# alarmclock3.net
KiCad netlist of a schematic drawn in EAGLE
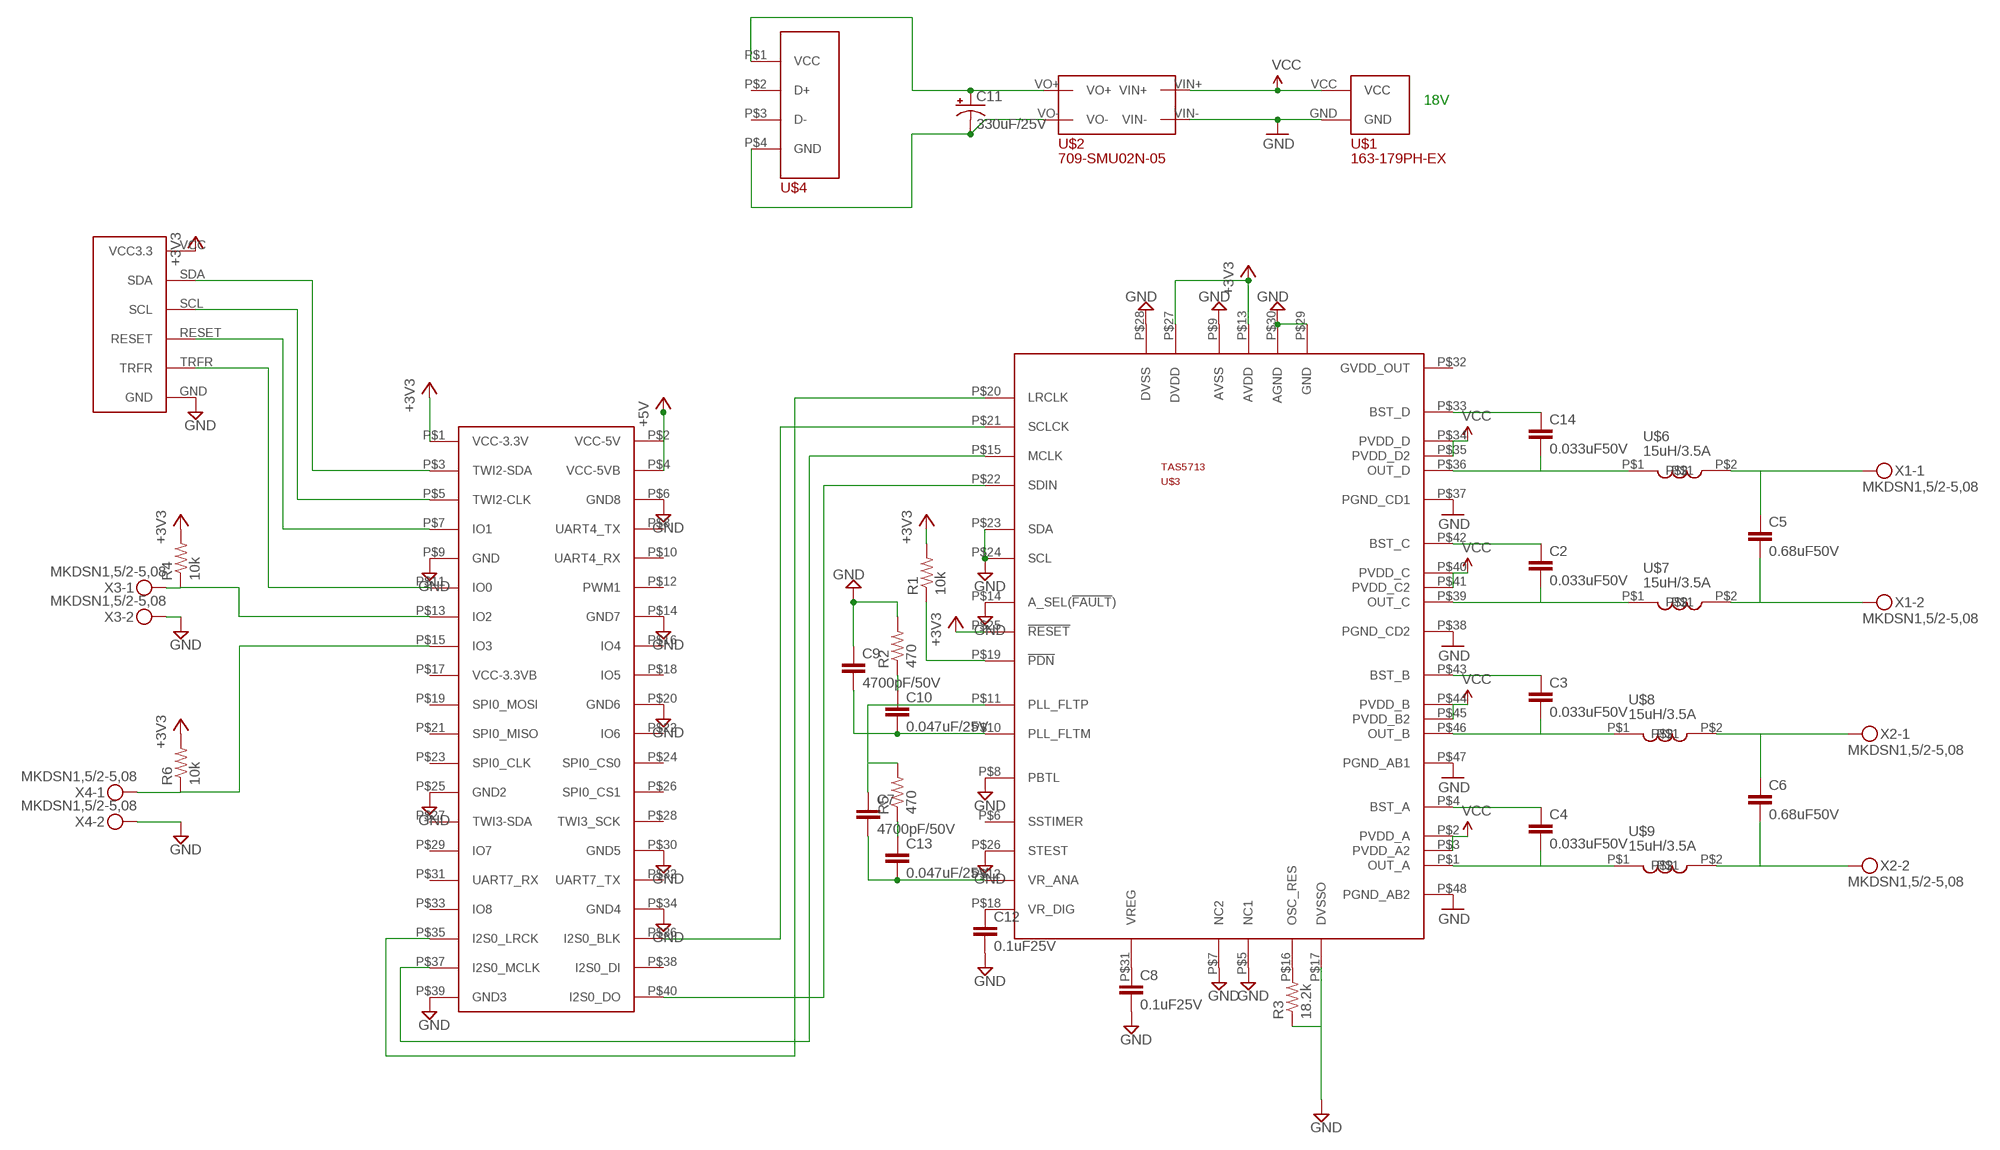
[diagram p0: schematic, sheet 1]

(export (version "E")
  (design (tool "Eeschema 10.0.6"))
  (components
    (comp (ref "C2")
      (value "0.033uF50V")
      (footprint "eagle-import:0603-CAP")
      (libsource (lib "eagle-import") (part "CAP0603-CAP"))
    )
    (comp (ref "C3")
      (value "0.033uF50V")
      (footprint "eagle-import:0603-CAP")
      (libsource (lib "eagle-import") (part "CAP0603-CAP"))
    )
    (comp (ref "C4")
      (value "0.033uF50V")
      (footprint "eagle-import:0603-CAP")
      (libsource (lib "eagle-import") (part "CAP0603-CAP"))
    )
    (comp (ref "C5")
      (value "0.68uF50V")
      (footprint "eagle-import:0603-CAP")
      (libsource (lib "eagle-import") (part "CAP0603-CAP"))
    )
    (comp (ref "C6")
      (value "0.68uF50V")
      (footprint "eagle-import:0603-CAP")
      (libsource (lib "eagle-import") (part "CAP0603-CAP"))
    )
    (comp (ref "C7")
      (value "4700pF/50V")
      (footprint "eagle-import:0603-CAP")
      (libsource (lib "eagle-import") (part "CAP0603-CAP"))
    )
    (comp (ref "C8")
      (value "0.1uF25V")
      (footprint "eagle-import:0603-CAP")
      (libsource (lib "eagle-import") (part "CAP0603-CAP"))
    )
    (comp (ref "C9")
      (value "4700pF/50V")
      (footprint "eagle-import:0603-CAP")
      (libsource (lib "eagle-import") (part "CAP0603-CAP"))
    )
    (comp (ref "C10")
      (value "0.047uF/25V")
      (footprint "eagle-import:0603-CAP")
      (libsource (lib "eagle-import") (part "CAP0603-CAP"))
    )
    (comp (ref "C11")
      (value "330uF/25V")
      (footprint "eagle-import:CPOL-RADIAL-10UF-25V")
      (libsource (lib "eagle-import") (part "CAP_POLPTH2"))
    )
    (comp (ref "C12")
      (value "0.1uF25V")
      (footprint "eagle-import:0603-CAP")
      (libsource (lib "eagle-import") (part "CAP0603-CAP"))
    )
    (comp (ref "C13")
      (value "0.047uF/25V")
      (footprint "eagle-import:0603-CAP")
      (libsource (lib "eagle-import") (part "CAP0603-CAP"))
    )
    (comp (ref "C14")
      (value "0.033uF50V")
      (footprint "eagle-import:0603-CAP")
      (libsource (lib "eagle-import") (part "CAP0603-CAP"))
    )
    (comp (ref "R1")
      (value "10k")
      (footprint "eagle-import:0603-RES")
      (libsource (lib "eagle-import") (part "RESISTOR0603-RES"))
    )
    (comp (ref "R2")
      (value "470")
      (footprint "eagle-import:0603-RES")
      (libsource (lib "eagle-import") (part "RESISTOR0603-RES"))
    )
    (comp (ref "R3")
      (value "18.2k")
      (footprint "eagle-import:0603-RES")
      (libsource (lib "eagle-import") (part "RESISTOR0603-RES"))
    )
    (comp (ref "R4")
      (value "10k")
      (footprint "eagle-import:0603-RES")
      (libsource (lib "eagle-import") (part "RESISTOR0603-RES"))
    )
    (comp (ref "R5")
      (value "470")
      (footprint "eagle-import:0603-RES")
      (libsource (lib "eagle-import") (part "RESISTOR0603-RES"))
    )
    (comp (ref "R6")
      (value "10k")
      (footprint "eagle-import:0603-RES")
      (libsource (lib "eagle-import") (part "RESISTOR0603-RES"))
    )
    (comp (ref "U$1")
      (value "163-179PH-EX")
      (footprint "eagle-import:163-179PH-EX_DIM")
      (libsource (lib "eagle-import") (part "163-179PH-EX"))
    )
    (comp (ref "U$2")
      (value "709-SMU02N-05")
      (footprint "eagle-import:709-SMU02N-05_DIM")
      (libsource (lib "eagle-import") (part "709-SMU02N-05"))
    )
    (comp (ref "U$3")
      (value "TAS5713")
      (footprint "eagle-import:TAS5713_DIM")
      (libsource (lib "eagle-import") (part "TAS5713"))
    )
    (comp (ref "U$4")
      (value "USB_TYPEA_CONNECTOR")
      (footprint "eagle-import:USB_DIM")
      (libsource (lib "eagle-import") (part "USB_TYPEA_CONNECTOR"))
    )
    (comp (ref "U$5")
      (value "BANANAPRO-CON6")
      (footprint "eagle-import:BANANAPRO-CON6_DIM")
      (libsource (lib "eagle-import") (part "BANANAPRO-CON6"))
    )
    (comp (ref "U$6")
      (value "15uH/3.5A")
      (footprint "eagle-import:MSS1260_DIM")
      (libsource (lib "eagle-import") (part "MSS1260INDUCTOR"))
    )
    (comp (ref "U$7")
      (value "15uH/3.5A")
      (footprint "eagle-import:MSS1260_DIM")
      (libsource (lib "eagle-import") (part "MSS1260INDUCTOR"))
    )
    (comp (ref "U$8")
      (value "15uH/3.5A")
      (footprint "eagle-import:MSS1260_DIM")
      (libsource (lib "eagle-import") (part "MSS1260INDUCTOR"))
    )
    (comp (ref "U$9")
      (value "15uH/3.5A")
      (footprint "eagle-import:MSS1260_DIM")
      (libsource (lib "eagle-import") (part "MSS1260INDUCTOR"))
    )
    (comp (ref "U$10")
      (value "SKYWRITER")
      (footprint "eagle-import:SKYWRITER_DIM")
      (libsource (lib "eagle-import") (part "SKYWRITER"))
    )
    (comp (ref "X1")
      (value "MKDSN1,5/2-5,08")
      (footprint "eagle-import:MKDSN1,5_2-5,08")
      (libsource (lib "eagle-import") (part "MKDSN1,5/2-5,08"))
    )
    (comp (ref "X2")
      (value "MKDSN1,5/2-5,08")
      (footprint "eagle-import:MKDSN1,5_2-5,08")
      (libsource (lib "eagle-import") (part "MKDSN1,5/2-5,08"))
    )
    (comp (ref "X3")
      (value "MKDSN1,5/2-5,08")
      (footprint "eagle-import:MKDSN1,5_2-5,08")
      (libsource (lib "eagle-import") (part "MKDSN1,5/2-5,08"))
    )
    (comp (ref "X4")
      (value "MKDSN1,5/2-5,08")
      (footprint "eagle-import:MKDSN1,5_2-5,08")
      (libsource (lib "eagle-import") (part "MKDSN1,5/2-5,08"))
    )
  )
  (nets
    (net (code "1") (name "+3V3") (class "Default")
      (node (ref "R1") (pin "2") (pinfunction "2_2") (pintype "passive"))
      (node (ref "R4") (pin "2") (pinfunction "2_2") (pintype "passive"))
      (node (ref "R6") (pin "2") (pinfunction "2_2") (pintype "passive"))
      (node (ref "U$10") (pin "VCC") (pinfunction "VCC3.3_VCC") (pintype "bidirectional"))
      (node (ref "U$3") (pin "P$13") (pinfunction "AVDD_P$13") (pintype "bidirectional"))
      (node (ref "U$3") (pin "P$25") (pinfunction "~{RESET}_P$25") (pintype "bidirectional"))
      (node (ref "U$3") (pin "P$27") (pinfunction "DVDD_P$27") (pintype "bidirectional"))
      (node (ref "U$5") (pin "P$1") (pinfunction "VCC-3.3V_P$1") (pintype "bidirectional"))
    )
    (net (code "2") (name "+5V") (class "Default")
      (node (ref "U$5") (pin "P$2") (pinfunction "VCC-5V_P$2") (pintype "bidirectional"))
      (node (ref "U$5") (pin "P$4") (pinfunction "VCC-5VB_P$4") (pintype "bidirectional"))
    )
    (net (code "3") (name "GND") (class "Default")
      (node (ref "C12") (pin "2") (pinfunction "2_2") (pintype "passive"))
      (node (ref "C8") (pin "2") (pinfunction "2_2") (pintype "passive"))
      (node (ref "C9") (pin "1") (pinfunction "1_1") (pintype "passive"))
      (node (ref "R2") (pin "2") (pinfunction "2_2") (pintype "passive"))
      (node (ref "R3") (pin "1") (pinfunction "1_1") (pintype "passive"))
      (node (ref "U$1") (pin "GND") (pinfunction "GND_GND") (pintype "bidirectional"))
      (node (ref "U$10") (pin "GND") (pinfunction "GND_GND") (pintype "bidirectional"))
      (node (ref "U$2") (pin "VIN-") (pinfunction "VIN-_VIN-") (pintype "bidirectional"))
      (node (ref "U$3") (pin "P$14") (pinfunction "A_SEL(~{FAULT})_P$14") (pintype "bidirectional"))
      (node (ref "U$3") (pin "P$17") (pinfunction "DVSSO_P$17") (pintype "bidirectional"))
      (node (ref "U$3") (pin "P$23") (pinfunction "SDA_P$23") (pintype "bidirectional"))
      (node (ref "U$3") (pin "P$24") (pinfunction "SCL_P$24") (pintype "bidirectional"))
      (node (ref "U$3") (pin "P$26") (pinfunction "STEST_P$26") (pintype "bidirectional"))
      (node (ref "U$3") (pin "P$28") (pinfunction "DVSS_P$28") (pintype "bidirectional"))
      (node (ref "U$3") (pin "P$29") (pinfunction "GND_P$29") (pintype "bidirectional"))
      (node (ref "U$3") (pin "P$30") (pinfunction "AGND_P$30") (pintype "bidirectional"))
      (node (ref "U$3") (pin "P$37") (pinfunction "PGND_CD1_P$37") (pintype "bidirectional"))
      (node (ref "U$3") (pin "P$38") (pinfunction "PGND_CD2_P$38") (pintype "bidirectional"))
      (node (ref "U$3") (pin "P$47") (pinfunction "PGND_AB1_P$47") (pintype "bidirectional"))
      (node (ref "U$3") (pin "P$48") (pinfunction "PGND_AB2_P$48") (pintype "bidirectional"))
      (node (ref "U$3") (pin "P$5") (pinfunction "NC1_P$5") (pintype "bidirectional"))
      (node (ref "U$3") (pin "P$7") (pinfunction "NC2_P$7") (pintype "bidirectional"))
      (node (ref "U$3") (pin "P$8") (pinfunction "PBTL_P$8") (pintype "bidirectional"))
      (node (ref "U$3") (pin "P$9") (pinfunction "AVSS_P$9") (pintype "bidirectional"))
      (node (ref "U$5") (pin "P$14") (pinfunction "GND7_P$14") (pintype "bidirectional"))
      (node (ref "U$5") (pin "P$20") (pinfunction "GND6_P$20") (pintype "bidirectional"))
      (node (ref "U$5") (pin "P$25") (pinfunction "GND2_P$25") (pintype "bidirectional"))
      (node (ref "U$5") (pin "P$30") (pinfunction "GND5_P$30") (pintype "bidirectional"))
      (node (ref "U$5") (pin "P$34") (pinfunction "GND4_P$34") (pintype "bidirectional"))
      (node (ref "U$5") (pin "P$39") (pinfunction "GND3_P$39") (pintype "bidirectional"))
      (node (ref "U$5") (pin "P$6") (pinfunction "GND8_P$6") (pintype "bidirectional"))
      (node (ref "U$5") (pin "P$9") (pinfunction "GND_P$9") (pintype "bidirectional"))
      (node (ref "X3") (pin "2") (pinfunction "KL_2") (pintype "passive"))
      (node (ref "X4") (pin "2") (pinfunction "KL_2") (pintype "passive"))
    )
    (net (code "4") (name "Net-(C10-Pad1)") (class "Default")
      (node (ref "C10") (pin "1") (pinfunction "1_1") (pintype "passive"))
      (node (ref "R2") (pin "1") (pinfunction "1_1") (pintype "passive"))
    )
    (net (code "5") (name "Net-(C11-+)") (class "Default")
      (node (ref "C11") (pin "1") (pinfunction "+_1") (pintype "passive"))
      (node (ref "U$2") (pin "VO+") (pinfunction "VO+_VO+") (pintype "bidirectional"))
      (node (ref "U$4") (pin "P$1") (pinfunction "VCC_P$1") (pintype "bidirectional"))
    )
    (net (code "6") (name "Net-(C11--)") (class "Default")
      (node (ref "C11") (pin "2") (pinfunction "-_2") (pintype "passive"))
      (node (ref "U$2") (pin "VO-") (pinfunction "VO-_VO-") (pintype "bidirectional"))
      (node (ref "U$4") (pin "P$4") (pinfunction "GND_P$4") (pintype "bidirectional"))
    )
    (net (code "7") (name "Net-(C13-Pad1)") (class "Default")
      (node (ref "C13") (pin "1") (pinfunction "1_1") (pintype "passive"))
      (node (ref "R5") (pin "1") (pinfunction "1_1") (pintype "passive"))
    )
    (net (code "8") (name "Net-(U$3-BST_A)") (class "Default")
      (node (ref "C4") (pin "1") (pinfunction "1_1") (pintype "passive"))
      (node (ref "U$3") (pin "P$4") (pinfunction "BST_A_P$4") (pintype "bidirectional"))
    )
    (net (code "9") (name "Net-(U$3-BST_B)") (class "Default")
      (node (ref "C3") (pin "1") (pinfunction "1_1") (pintype "passive"))
      (node (ref "U$3") (pin "P$43") (pinfunction "BST_B_P$43") (pintype "bidirectional"))
    )
    (net (code "10") (name "Net-(U$3-BST_C)") (class "Default")
      (node (ref "C2") (pin "1") (pinfunction "1_1") (pintype "passive"))
      (node (ref "U$3") (pin "P$42") (pinfunction "BST_C_P$42") (pintype "bidirectional"))
    )
    (net (code "11") (name "Net-(U$3-BST_D)") (class "Default")
      (node (ref "C14") (pin "1") (pinfunction "1_1") (pintype "passive"))
      (node (ref "U$3") (pin "P$33") (pinfunction "BST_D_P$33") (pintype "bidirectional"))
    )
    (net (code "12") (name "Net-(U$3-LRCLK)") (class "Default")
      (node (ref "U$3") (pin "P$20") (pinfunction "LRCLK_P$20") (pintype "bidirectional"))
      (node (ref "U$5") (pin "P$35") (pinfunction "I2S0_LRCK_P$35") (pintype "bidirectional"))
    )
    (net (code "13") (name "Net-(U$3-MCLK)") (class "Default")
      (node (ref "U$3") (pin "P$15") (pinfunction "MCLK_P$15") (pintype "bidirectional"))
      (node (ref "U$5") (pin "P$37") (pinfunction "I2S0_MCLK_P$37") (pintype "bidirectional"))
    )
    (net (code "14") (name "Net-(U$3-OSC_RES)") (class "Default")
      (node (ref "R3") (pin "2") (pinfunction "2_2") (pintype "passive"))
      (node (ref "U$3") (pin "P$16") (pinfunction "OSC_RES_P$16") (pintype "bidirectional"))
    )
    (net (code "15") (name "Net-(U$3-OUT_A)") (class "Default")
      (node (ref "C4") (pin "2") (pinfunction "2_2") (pintype "passive"))
      (node (ref "U$3") (pin "P$1") (pinfunction "OUT_A_P$1") (pintype "bidirectional"))
      (node (ref "U$9") (pin "P$1") (pinfunction "P$1_P$1") (pintype "bidirectional"))
    )
    (net (code "16") (name "Net-(U$3-OUT_B)") (class "Default")
      (node (ref "C3") (pin "2") (pinfunction "2_2") (pintype "passive"))
      (node (ref "U$3") (pin "P$46") (pinfunction "OUT_B_P$46") (pintype "bidirectional"))
      (node (ref "U$8") (pin "P$1") (pinfunction "P$1_P$1") (pintype "bidirectional"))
    )
    (net (code "17") (name "Net-(U$3-OUT_C)") (class "Default")
      (node (ref "C2") (pin "2") (pinfunction "2_2") (pintype "passive"))
      (node (ref "U$3") (pin "P$39") (pinfunction "OUT_C_P$39") (pintype "bidirectional"))
      (node (ref "U$7") (pin "P$1") (pinfunction "P$1_P$1") (pintype "bidirectional"))
    )
    (net (code "18") (name "Net-(U$3-OUT_D)") (class "Default")
      (node (ref "C14") (pin "2") (pinfunction "2_2") (pintype "passive"))
      (node (ref "U$3") (pin "P$36") (pinfunction "OUT_D_P$36") (pintype "bidirectional"))
      (node (ref "U$6") (pin "P$1") (pinfunction "P$1_P$1") (pintype "bidirectional"))
    )
    (net (code "19") (name "Net-(U$3-PLL_FLTM)") (class "Default")
      (node (ref "C10") (pin "2") (pinfunction "2_2") (pintype "passive"))
      (node (ref "C9") (pin "2") (pinfunction "2_2") (pintype "passive"))
      (node (ref "U$3") (pin "P$10") (pinfunction "PLL_FLTM_P$10") (pintype "bidirectional"))
    )
    (net (code "20") (name "Net-(U$3-PLL_FLTP)") (class "Default")
      (node (ref "C7") (pin "1") (pinfunction "1_1") (pintype "passive"))
      (node (ref "R5") (pin "2") (pinfunction "2_2") (pintype "passive"))
      (node (ref "U$3") (pin "P$11") (pinfunction "PLL_FLTP_P$11") (pintype "bidirectional"))
    )
    (net (code "21") (name "Net-(U$3-SCLCK)") (class "Default")
      (node (ref "U$3") (pin "P$21") (pinfunction "SCLCK_P$21") (pintype "bidirectional"))
      (node (ref "U$5") (pin "P$36") (pinfunction "I2S0_BLK_P$36") (pintype "bidirectional"))
    )
    (net (code "22") (name "Net-(U$3-SDIN)") (class "Default")
      (node (ref "U$3") (pin "P$22") (pinfunction "SDIN_P$22") (pintype "bidirectional"))
      (node (ref "U$5") (pin "P$40") (pinfunction "I2S0_DO_P$40") (pintype "bidirectional"))
    )
    (net (code "23") (name "Net-(U$3-VREG)") (class "Default")
      (node (ref "C8") (pin "1") (pinfunction "1_1") (pintype "passive"))
      (node (ref "U$3") (pin "P$31") (pinfunction "VREG_P$31") (pintype "bidirectional"))
    )
    (net (code "24") (name "Net-(U$3-VR_ANA)") (class "Default")
      (node (ref "C13") (pin "2") (pinfunction "2_2") (pintype "passive"))
      (node (ref "C7") (pin "2") (pinfunction "2_2") (pintype "passive"))
      (node (ref "U$3") (pin "P$12") (pinfunction "VR_ANA_P$12") (pintype "bidirectional"))
    )
    (net (code "25") (name "Net-(U$3-VR_DIG)") (class "Default")
      (node (ref "C12") (pin "1") (pinfunction "1_1") (pintype "passive"))
      (node (ref "U$3") (pin "P$18") (pinfunction "VR_DIG_P$18") (pintype "bidirectional"))
    )
    (net (code "26") (name "Net-(U$3-~{PDN})") (class "Default")
      (node (ref "R1") (pin "1") (pinfunction "1_1") (pintype "passive"))
      (node (ref "U$3") (pin "P$19") (pinfunction "~{PDN}_P$19") (pintype "bidirectional"))
    )
    (net (code "27") (name "Net-(U$5-IO0)") (class "Default")
      (node (ref "U$10") (pin "TRFR") (pinfunction "TRFR_TRFR") (pintype "bidirectional"))
      (node (ref "U$5") (pin "P$11") (pinfunction "IO0_P$11") (pintype "bidirectional"))
    )
    (net (code "28") (name "Net-(U$5-IO1)") (class "Default")
      (node (ref "U$10") (pin "RESET") (pinfunction "RESET_RESET") (pintype "bidirectional"))
      (node (ref "U$5") (pin "P$7") (pinfunction "IO1_P$7") (pintype "bidirectional"))
    )
    (net (code "29") (name "Net-(U$5-IO2)") (class "Default")
      (node (ref "R4") (pin "1") (pinfunction "1_1") (pintype "passive"))
      (node (ref "U$5") (pin "P$13") (pinfunction "IO2_P$13") (pintype "bidirectional"))
      (node (ref "X3") (pin "1") (pinfunction "KL_1") (pintype "passive"))
    )
    (net (code "30") (name "Net-(U$5-IO3)") (class "Default")
      (node (ref "R6") (pin "1") (pinfunction "1_1") (pintype "passive"))
      (node (ref "U$5") (pin "P$15") (pinfunction "IO3_P$15") (pintype "bidirectional"))
      (node (ref "X4") (pin "1") (pinfunction "KL_1") (pintype "passive"))
    )
    (net (code "31") (name "Net-(U$5-TWI2-CLK)") (class "Default")
      (node (ref "U$10") (pin "SCL") (pinfunction "SCL_SCL") (pintype "bidirectional"))
      (node (ref "U$5") (pin "P$5") (pinfunction "TWI2-CLK_P$5") (pintype "bidirectional"))
    )
    (net (code "32") (name "Net-(U$5-TWI2-SDA)") (class "Default")
      (node (ref "U$10") (pin "SDA") (pinfunction "SDA_SDA") (pintype "bidirectional"))
      (node (ref "U$5") (pin "P$3") (pinfunction "TWI2-SDA_P$3") (pintype "bidirectional"))
    )
    (net (code "33") (name "Net-(X1A-KL)") (class "Default")
      (node (ref "C5") (pin "1") (pinfunction "1_1") (pintype "passive"))
      (node (ref "U$6") (pin "P$2") (pinfunction "P$2_P$2") (pintype "bidirectional"))
      (node (ref "X1") (pin "1") (pinfunction "KL_1") (pintype "passive"))
    )
    (net (code "34") (name "Net-(X1B-KL)") (class "Default")
      (node (ref "C5") (pin "2") (pinfunction "2_2") (pintype "passive"))
      (node (ref "U$7") (pin "P$2") (pinfunction "P$2_P$2") (pintype "bidirectional"))
      (node (ref "X1") (pin "2") (pinfunction "KL_2") (pintype "passive"))
    )
    (net (code "35") (name "Net-(X2A-KL)") (class "Default")
      (node (ref "C6") (pin "1") (pinfunction "1_1") (pintype "passive"))
      (node (ref "U$8") (pin "P$2") (pinfunction "P$2_P$2") (pintype "bidirectional"))
      (node (ref "X2") (pin "1") (pinfunction "KL_1") (pintype "passive"))
    )
    (net (code "36") (name "Net-(X2B-KL)") (class "Default")
      (node (ref "C6") (pin "2") (pinfunction "2_2") (pintype "passive"))
      (node (ref "U$9") (pin "P$2") (pinfunction "P$2_P$2") (pintype "bidirectional"))
      (node (ref "X2") (pin "2") (pinfunction "KL_2") (pintype "passive"))
    )
    (net (code "37") (name "VCC") (class "Default")
      (node (ref "U$1") (pin "VCC") (pinfunction "VCC_VCC") (pintype "bidirectional"))
      (node (ref "U$2") (pin "VIN+") (pinfunction "VIN+_VIN+") (pintype "bidirectional"))
      (node (ref "U$3") (pin "P$2") (pinfunction "PVDD_A_P$2") (pintype "bidirectional"))
      (node (ref "U$3") (pin "P$3") (pinfunction "PVDD_A2_P$3") (pintype "bidirectional"))
      (node (ref "U$3") (pin "P$34") (pinfunction "PVDD_D_P$34") (pintype "bidirectional"))
      (node (ref "U$3") (pin "P$35") (pinfunction "PVDD_D2_P$35") (pintype "bidirectional"))
      (node (ref "U$3") (pin "P$40") (pinfunction "PVDD_C_P$40") (pintype "bidirectional"))
      (node (ref "U$3") (pin "P$41") (pinfunction "PVDD_C2_P$41") (pintype "bidirectional"))
      (node (ref "U$3") (pin "P$44") (pinfunction "PVDD_B_P$44") (pintype "bidirectional"))
      (node (ref "U$3") (pin "P$45") (pinfunction "PVDD_B2_P$45") (pintype "bidirectional"))
    )
    (net (code "38") (name "unconnected-(U$3-GVDD_OUT-PadP$32)") (class "Default")
      (node (ref "U$3") (pin "P$32") (pinfunction "GVDD_OUT_P$32") (pintype "bidirectional"))
    )
    (net (code "39") (name "unconnected-(U$3-SSTIMER-PadP$6)") (class "Default")
      (node (ref "U$3") (pin "P$6") (pinfunction "SSTIMER_P$6") (pintype "bidirectional"))
    )
    (net (code "40") (name "unconnected-(U$4-D+-PadP$2)") (class "Default")
      (node (ref "U$4") (pin "P$2") (pinfunction "D+_P$2") (pintype "bidirectional"))
    )
    (net (code "41") (name "unconnected-(U$4-D--PadP$3)") (class "Default")
      (node (ref "U$4") (pin "P$3") (pinfunction "D-_P$3") (pintype "bidirectional"))
    )
    (net (code "42") (name "unconnected-(U$5-I2S0_DI-PadP$38)") (class "Default")
      (node (ref "U$5") (pin "P$38") (pinfunction "I2S0_DI_P$38") (pintype "bidirectional"))
    )
    (net (code "43") (name "unconnected-(U$5-IO4-PadP$16)") (class "Default")
      (node (ref "U$5") (pin "P$16") (pinfunction "IO4_P$16") (pintype "bidirectional"))
    )
    (net (code "44") (name "unconnected-(U$5-IO5-PadP$18)") (class "Default")
      (node (ref "U$5") (pin "P$18") (pinfunction "IO5_P$18") (pintype "bidirectional"))
    )
    (net (code "45") (name "unconnected-(U$5-IO6-PadP$22)") (class "Default")
      (node (ref "U$5") (pin "P$22") (pinfunction "IO6_P$22") (pintype "bidirectional"))
    )
    (net (code "46") (name "unconnected-(U$5-IO7-PadP$29)") (class "Default")
      (node (ref "U$5") (pin "P$29") (pinfunction "IO7_P$29") (pintype "bidirectional"))
    )
    (net (code "47") (name "unconnected-(U$5-IO8-PadP$33)") (class "Default")
      (node (ref "U$5") (pin "P$33") (pinfunction "IO8_P$33") (pintype "bidirectional"))
    )
    (net (code "48") (name "unconnected-(U$5-PWM1-PadP$12)") (class "Default")
      (node (ref "U$5") (pin "P$12") (pinfunction "PWM1_P$12") (pintype "bidirectional"))
    )
    (net (code "49") (name "unconnected-(U$5-SPI0_CLK-PadP$23)") (class "Default")
      (node (ref "U$5") (pin "P$23") (pinfunction "SPI0_CLK_P$23") (pintype "bidirectional"))
    )
    (net (code "50") (name "unconnected-(U$5-SPI0_CS0-PadP$24)") (class "Default")
      (node (ref "U$5") (pin "P$24") (pinfunction "SPI0_CS0_P$24") (pintype "bidirectional"))
    )
    (net (code "51") (name "unconnected-(U$5-SPI0_CS1-PadP$26)") (class "Default")
      (node (ref "U$5") (pin "P$26") (pinfunction "SPI0_CS1_P$26") (pintype "bidirectional"))
    )
    (net (code "52") (name "unconnected-(U$5-SPI0_MISO-PadP$21)") (class "Default")
      (node (ref "U$5") (pin "P$21") (pinfunction "SPI0_MISO_P$21") (pintype "bidirectional"))
    )
    (net (code "53") (name "unconnected-(U$5-SPI0_MOSI-PadP$19)") (class "Default")
      (node (ref "U$5") (pin "P$19") (pinfunction "SPI0_MOSI_P$19") (pintype "bidirectional"))
    )
    (net (code "54") (name "unconnected-(U$5-TWI3-SDA-PadP$27)") (class "Default")
      (node (ref "U$5") (pin "P$27") (pinfunction "TWI3-SDA_P$27") (pintype "bidirectional"))
    )
    (net (code "55") (name "unconnected-(U$5-TWI3_SCK-PadP$28)") (class "Default")
      (node (ref "U$5") (pin "P$28") (pinfunction "TWI3_SCK_P$28") (pintype "bidirectional"))
    )
    (net (code "56") (name "unconnected-(U$5-UART4_RX-PadP$10)") (class "Default")
      (node (ref "U$5") (pin "P$10") (pinfunction "UART4_RX_P$10") (pintype "bidirectional"))
    )
    (net (code "57") (name "unconnected-(U$5-UART4_TX-PadP$8)") (class "Default")
      (node (ref "U$5") (pin "P$8") (pinfunction "UART4_TX_P$8") (pintype "bidirectional"))
    )
    (net (code "58") (name "unconnected-(U$5-UART7_RX-PadP$31)") (class "Default")
      (node (ref "U$5") (pin "P$31") (pinfunction "UART7_RX_P$31") (pintype "bidirectional"))
    )
    (net (code "59") (name "unconnected-(U$5-UART7_TX-PadP$32)") (class "Default")
      (node (ref "U$5") (pin "P$32") (pinfunction "UART7_TX_P$32") (pintype "bidirectional"))
    )
    (net (code "60") (name "unconnected-(U$5-VCC-3.3VB-PadP$17)") (class "Default")
      (node (ref "U$5") (pin "P$17") (pinfunction "VCC-3.3VB_P$17") (pintype "bidirectional"))
    )
  )
)
